# H01R0_Frontend_1.net
KiCad netlist of a schematic drawn in Altium Designer
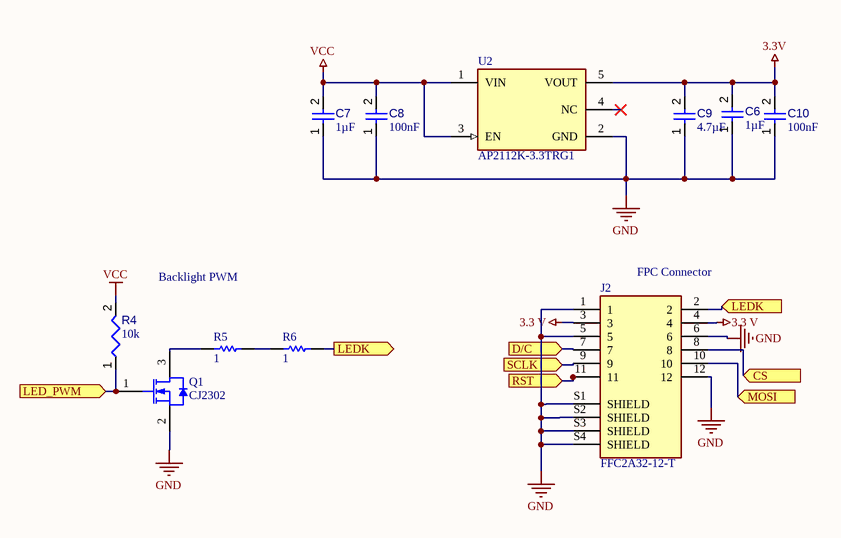
[diagram p0: H01R0_Frontend 1.SchDoc]

(export (version "E")
  (design (tool "Eeschema 10.0.6"))
  (components
    (comp (ref "C6")
      (value "1µF")
      (footprint "CAPC1608X90X35ML15T15")
      (description "Chip Capacitor, 1 uF, +/- 10%, 16 V, 0603 (1608 Metric)")
      (fields (field (name "TOLERANCE") "10%") (field (name "Comment") "Capacitor 1uF +/- 10% 16V 0603"))
      (libsource (lib "Hannah Nguyen") (part "CAP-NP-2"))
    )
    (comp (ref "C7")
      (value "1µF")
      (footprint "CAPC1608X90X35ML15T15")
      (description "Chip Capacitor, 1 uF, +/- 10%, 16 V, 0603 (1608 Metric)")
      (fields (field (name "TOLERANCE") "10%") (field (name "Comment") "Capacitor 1uF +/- 10% 16V 0603"))
      (libsource (lib "Hannah Nguyen") (part "CAP-NP-2"))
    )
    (comp (ref "C8")
      (value "100nF")
      (footprint "CAPC1005X56X25LL10T15")
      (description "Chip Capacitor, 0.1 uF, +/- 5%, 16 V, 0402 (1005 Metric)")
      (fields (field (name "TOLERANCE") "5%") (field (name "Comment") "Capacitor 0.1 uF +/- 5% 16 V 0402"))
      (libsource (lib "Hannah Nguyen") (part "CAP-NP-2"))
    )
    (comp (ref "C9")
      (value "4.7µF")
      (footprint "CAPC0805(2012)145_L")
      (description "Chip Capacitor, 4.7µF +/-40%, 25V, 0805, Thickness 1.45 mm")
      (fields (field (name "TOLERANCE") "20%") (field (name "Comment") "Capacitor 4.7µF +/-40% 25V 0805"))
      (libsource (lib "Hannah Nguyen") (part "CAP-NP-2"))
    )
    (comp (ref "C10")
      (value "100nF")
      (footprint "CAPC1005X56X25LL10T15")
      (description "Chip Capacitor, 0.1 uF, +/- 5%, 16 V, 0402 (1005 Metric)")
      (fields (field (name "TOLERANCE") "5%") (field (name "Comment") "Capacitor 0.1 uF +/- 5% 16 V 0402"))
      (libsource (lib "Hannah Nguyen") (part "CAP-NP-2"))
    )
    (comp (ref "J2")
      (value "FFC2A32-12-T")
      (footprint "GCT_FFC2A32-12-T")
      (description "12 Position FFC, FPC Connector Contacts, Vertical - 1 Sided 0.020 (0.50mm) Surface Mount")
      (fields (field (name "MF") "Global Connector Technology"))
      (libsource (lib "Hannah Nguyen") (part "FFC2A32-12-T"))
    )
    (comp (ref "Q1")
      (value "CJ2302")
      (footprint "JSCJ-SOT23-3_V")
      (description "N-Channe Plastic Encapsulate MOSFET, 20 V, 2.1 A, 3-Pin SOT23, Tape and Reel")
      (fields (field (name "MANUFACTURER") "Jiangsu Changjiang Electronics Technology"))
      (libsource (lib "Hannah Nguyen") (part "NEMOS-GSD-3"))
    )
    (comp (ref "R4")
      (value "10k")
      (footprint "RESC0402(1005)_L")
      (description "10K 0.063W 1% 0402 (1005 Metric)  SMD")
      (fields (field (name "POWER") "63mW") (field (name "TOLERANCE") "1%"))
      (libsource (lib "Hannah Nguyen") (part "10KR2F"))
    )
    (comp (ref "R5")
      (value "1")
      (footprint "RESC2013X50X35ML15T15")
      (description "Chip Resistor, 0 Ohm, +/- 1%, 125 mW, -55 to 155 degC, 0805 (2012 Metric)")
      (fields (field (name "TOLERANCE") "1%") (field (name "POWER") "125mW"))
      (libsource (lib "Hannah Nguyen") (part "RES-2"))
    )
    (comp (ref "R6")
      (value "1")
      (footprint "RESC2013X50X35ML15T15")
      (description "Chip Resistor, 0 Ohm, +/- 1%, 125 mW, -55 to 155 degC, 0805 (2012 Metric)")
      (fields (field (name "TOLERANCE") "1%") (field (name "POWER") "125mW"))
      (libsource (lib "Hannah Nguyen") (part "RES-2"))
    )
    (comp (ref "U2")
      (value "AP2112K-3.3TRG1")
      (footprint "FP-SOT25-IPC_A")
      (description "IC REG LINEAR 3.3V 600MA SOT25")
      (libsource (lib "Altium Content Vault") (part "c8ab751aee5229183125ab046a11caa"))
    )
  )
  (nets
    (net (code "1") (name "/CS") (class "Default")
      (node (ref "J2") (pin "8") (pinfunction "8_8") (pintype "passive"))
    )
    (net (code "2") (name "/D{slash}C") (class "Default")
      (node (ref "J2") (pin "7") (pinfunction "7_7") (pintype "passive"))
    )
    (net (code "3") (name "/LEDK") (class "Default")
      (node (ref "J2") (pin "2") (pinfunction "2_2") (pintype "passive"))
      (node (ref "R6") (pin "2") (pinfunction "2_2") (pintype "passive"))
    )
    (net (code "4") (name "/LED_PWM") (class "Default")
      (node (ref "Q1") (pin "1") (pinfunction "G_1") (pintype "passive"))
      (node (ref "R4") (pin "1") (pinfunction "1_1") (pintype "passive"))
    )
    (net (code "5") (name "/MOSI") (class "Default")
      (node (ref "J2") (pin "10") (pinfunction "10_10") (pintype "passive"))
    )
    (net (code "6") (name "/RST") (class "Default")
      (node (ref "J2") (pin "11") (pinfunction "11_11") (pintype "passive"))
    )
    (net (code "7") (name "/SCLK") (class "Default")
      (node (ref "J2") (pin "9") (pinfunction "9_9") (pintype "passive"))
    )
    (net (code "8") (name "3.3 V") (class "Default")
      (node (ref "J2") (pin "3") (pinfunction "3_3") (pintype "passive"))
      (node (ref "J2") (pin "4") (pinfunction "4_4") (pintype "passive"))
    )
    (net (code "9") (name "3.3V") (class "Default")
      (node (ref "C10") (pin "2") (pinfunction "2_2") (pintype "passive"))
      (node (ref "C6") (pin "2") (pinfunction "2_2") (pintype "passive"))
      (node (ref "C9") (pin "2") (pinfunction "2_2") (pintype "passive"))
      (node (ref "U2") (pin "5") (pinfunction "VOUT_5") (pintype "power_in"))
    )
    (net (code "10") (name "GND") (class "Default")
      (node (ref "C10") (pin "1") (pinfunction "1_1") (pintype "passive"))
      (node (ref "C6") (pin "1") (pinfunction "1_1") (pintype "passive"))
      (node (ref "C7") (pin "1") (pinfunction "1_1") (pintype "passive"))
      (node (ref "C8") (pin "1") (pinfunction "1_1") (pintype "passive"))
      (node (ref "C9") (pin "1") (pinfunction "1_1") (pintype "passive"))
      (node (ref "J2") (pin "1") (pinfunction "1_1") (pintype "passive"))
      (node (ref "J2") (pin "12") (pinfunction "12_12") (pintype "passive"))
      (node (ref "J2") (pin "5") (pinfunction "5_5") (pintype "passive"))
      (node (ref "J2") (pin "6") (pinfunction "6_6") (pintype "passive"))
      (node (ref "J2") (pin "S1") (pinfunction "SHIELD_S1") (pintype "passive"))
      (node (ref "J2") (pin "S2") (pinfunction "SHIELD_S2") (pintype "passive"))
      (node (ref "J2") (pin "S3") (pinfunction "SHIELD_S3") (pintype "passive"))
      (node (ref "J2") (pin "S4") (pinfunction "SHIELD_S4") (pintype "passive"))
      (node (ref "Q1") (pin "2") (pinfunction "S_2") (pintype "passive"))
      (node (ref "U2") (pin "2") (pinfunction "GND_2") (pintype "power_in"))
    )
    (net (code "11") (name "Net-(Q1-D)") (class "Default")
      (node (ref "Q1") (pin "3") (pinfunction "D_3") (pintype "passive"))
      (node (ref "R5") (pin "1") (pinfunction "1_1") (pintype "passive"))
    )
    (net (code "12") (name "Net-(R5-Pad2)") (class "Default")
      (node (ref "R5") (pin "2") (pinfunction "2_2") (pintype "passive"))
      (node (ref "R6") (pin "1") (pinfunction "1_1") (pintype "passive"))
    )
    (net (code "13") (name "VCC") (class "Default")
      (node (ref "C7") (pin "2") (pinfunction "2_2") (pintype "passive"))
      (node (ref "C8") (pin "2") (pinfunction "2_2") (pintype "passive"))
      (node (ref "R4") (pin "2") (pinfunction "2_2") (pintype "passive"))
      (node (ref "U2") (pin "1") (pinfunction "VIN_1") (pintype "power_in"))
      (node (ref "U2") (pin "3") (pinfunction "EN_3") (pintype "input"))
    )
    (net (code "14") (name "unconnected-(U2-NC-Pad4)") (class "Default")
      (node (ref "U2") (pin "4") (pinfunction "NC_4") (pintype "passive+no_connect"))
    )
  )
)
